# Acoustic_Cam.net
KiCad netlist of a schematic drawn in Altium Designer
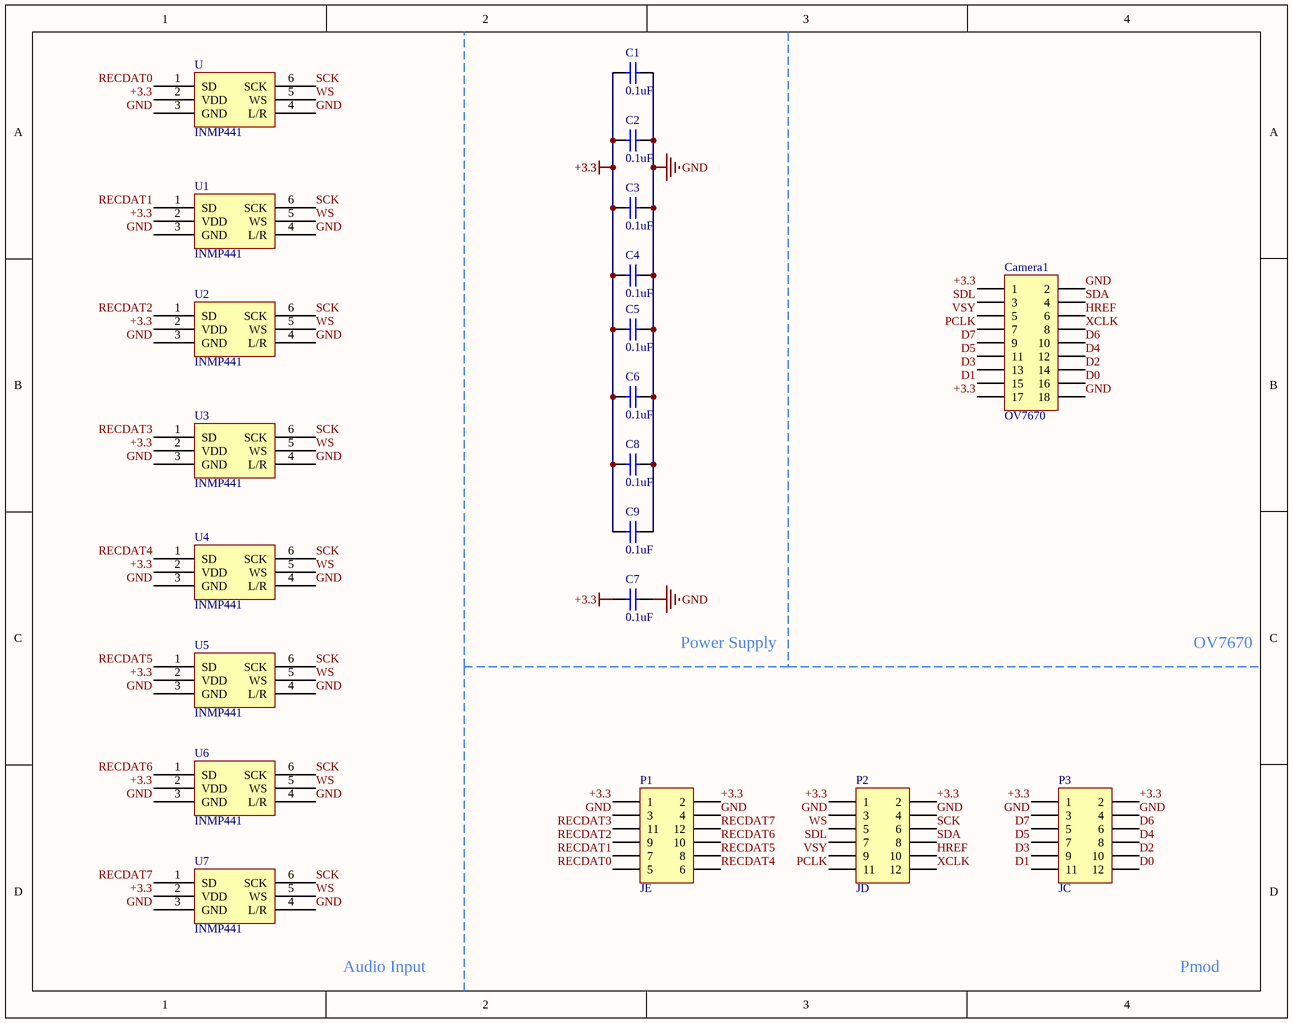
[diagram p0: Acoustic_Cam.SchDoc]

(export (version "E")
  (design (tool "Eeschema 10.0.6"))
  (components
    (comp (ref "C1")
      (value "0.1uF")
      (footprint "0603-1")
      (description "Capacitor")
      (fields (field (name "PUBLISHER") "Altium Limited"))
      (libsource (lib "Miscellaneous Devices") (part "Cap"))
    )
    (comp (ref "C2")
      (value "0.1uF")
      (footprint "0603-1")
      (description "Capacitor")
      (fields (field (name "PUBLISHER") "Altium Limited"))
      (libsource (lib "Miscellaneous Devices") (part "Cap"))
    )
    (comp (ref "C3")
      (value "0.1uF")
      (footprint "0603-1")
      (description "Capacitor")
      (fields (field (name "PUBLISHER") "Altium Limited"))
      (libsource (lib "Miscellaneous Devices") (part "Cap"))
    )
    (comp (ref "C4")
      (value "0.1uF")
      (footprint "0603-1")
      (description "Capacitor")
      (fields (field (name "PUBLISHER") "Altium Limited"))
      (libsource (lib "Miscellaneous Devices") (part "Cap"))
    )
    (comp (ref "C5")
      (value "0.1uF")
      (footprint "0603-1")
      (description "Capacitor")
      (fields (field (name "PUBLISHER") "Altium Limited"))
      (libsource (lib "Miscellaneous Devices") (part "Cap"))
    )
    (comp (ref "C6")
      (value "0.1uF")
      (footprint "0603-1")
      (description "Capacitor")
      (fields (field (name "PUBLISHER") "Altium Limited"))
      (libsource (lib "Miscellaneous Devices") (part "Cap"))
    )
    (comp (ref "C7")
      (value "0.1uF")
      (footprint "0603-1")
      (description "Capacitor")
      (fields (field (name "PUBLISHER") "Altium Limited"))
      (libsource (lib "Miscellaneous Devices") (part "Cap"))
    )
    (comp (ref "C8")
      (value "0.1uF")
      (footprint "0603-1")
      (description "Capacitor")
      (fields (field (name "PUBLISHER") "Altium Limited"))
      (libsource (lib "Miscellaneous Devices") (part "Cap"))
    )
    (comp (ref "C9")
      (value "0.1uF")
      (footprint "0603-1")
      (description "Capacitor")
      (fields (field (name "PUBLISHER") "Altium Limited"))
      (libsource (lib "Miscellaneous Devices") (part "Cap"))
    )
    (comp (ref "Camera1")
      (value "OV7670")
      (footprint "HDR2X9")
      (description "Header, 9-Pin, Dual row")
      (fields (field (name "PUBLISHER") "Altium Limited"))
      (libsource (lib "Miscellaneous Connectors") (part "Header 9X2"))
    )
    (comp (ref "P1")
      (value "JE")
      (footprint "HDR2X6")
      (description "Header, 6-Pin, Dual row")
      (fields (field (name "PUBLISHER") "Altium Limited"))
      (libsource (lib "") (part "Header 6X2_1"))
    )
    (comp (ref "P2")
      (value "JD")
      (footprint "HDR2X6")
      (description "Header, 6-Pin, Dual row")
      (fields (field (name "PUBLISHER") "Altium Limited"))
      (libsource (lib "Miscellaneous Connectors") (part "Header 6X2"))
    )
    (comp (ref "P3")
      (value "JC")
      (footprint "HDR2X6")
      (description "Header, 6-Pin, Dual row")
      (fields (field (name "PUBLISHER") "Altium Limited"))
      (libsource (lib "Miscellaneous Connectors") (part "Header 6X2"))
    )
    (comp (ref "U") (value "INMP441") (footprint "INMP441board") (libsource (lib "Schlib2") (part "INMP441")))
    (comp (ref "U1")
      (value "INMP441")
      (footprint "INMP441board")
      (libsource (lib "Schlib2") (part "INMP441"))
    )
    (comp (ref "U2")
      (value "INMP441")
      (footprint "INMP441board")
      (libsource (lib "Schlib2") (part "INMP441"))
    )
    (comp (ref "U3")
      (value "INMP441")
      (footprint "INMP441board")
      (libsource (lib "Schlib2") (part "INMP441"))
    )
    (comp (ref "U4")
      (value "INMP441")
      (footprint "INMP441board")
      (libsource (lib "Schlib2") (part "INMP441"))
    )
    (comp (ref "U5")
      (value "INMP441")
      (footprint "INMP441board")
      (libsource (lib "Schlib2") (part "INMP441"))
    )
    (comp (ref "U6")
      (value "INMP441")
      (footprint "INMP441board")
      (libsource (lib "Schlib2") (part "INMP441"))
    )
    (comp (ref "U7")
      (value "INMP441")
      (footprint "INMP441board")
      (libsource (lib "Schlib2") (part "INMP441"))
    )
  )
  (nets
    (net (code "1") (name "+3.3") (class "Default")
      (node (ref "C1") (pin "1") (pinfunction "1_1") (pintype "passive"))
      (node (ref "C2") (pin "1") (pinfunction "1_1") (pintype "passive"))
      (node (ref "C3") (pin "1") (pinfunction "1_1") (pintype "passive"))
      (node (ref "C4") (pin "1") (pinfunction "1_1") (pintype "passive"))
      (node (ref "C5") (pin "1") (pinfunction "1_1") (pintype "passive"))
      (node (ref "C6") (pin "1") (pinfunction "1_1") (pintype "passive"))
      (node (ref "C7") (pin "1") (pinfunction "1_1") (pintype "passive"))
      (node (ref "C8") (pin "1") (pinfunction "1_1") (pintype "passive"))
      (node (ref "C9") (pin "1") (pinfunction "1_1") (pintype "passive"))
      (node (ref "Camera1") (pin "1") (pinfunction "1_1") (pintype "passive"))
      (node (ref "Camera1") (pin "17") (pinfunction "17_17") (pintype "passive"))
      (node (ref "P1") (pin "1") (pinfunction "1_1") (pintype "passive"))
      (node (ref "P1") (pin "2") (pinfunction "2_2") (pintype "passive"))
      (node (ref "P2") (pin "1") (pinfunction "1_1") (pintype "passive"))
      (node (ref "P2") (pin "2") (pinfunction "2_2") (pintype "passive"))
      (node (ref "P3") (pin "1") (pinfunction "1_1") (pintype "passive"))
      (node (ref "P3") (pin "2") (pinfunction "2_2") (pintype "passive"))
      (node (ref "U") (pin "2") (pinfunction "VDD_2") (pintype "passive"))
      (node (ref "U1") (pin "2") (pinfunction "VDD_2") (pintype "passive"))
      (node (ref "U2") (pin "2") (pinfunction "VDD_2") (pintype "passive"))
      (node (ref "U3") (pin "2") (pinfunction "VDD_2") (pintype "passive"))
      (node (ref "U4") (pin "2") (pinfunction "VDD_2") (pintype "passive"))
      (node (ref "U5") (pin "2") (pinfunction "VDD_2") (pintype "passive"))
      (node (ref "U6") (pin "2") (pinfunction "VDD_2") (pintype "passive"))
      (node (ref "U7") (pin "2") (pinfunction "VDD_2") (pintype "passive"))
    )
    (net (code "2") (name "/D0") (class "Default")
      (node (ref "Camera1") (pin "16") (pinfunction "16_16") (pintype "passive"))
      (node (ref "P3") (pin "12") (pinfunction "12_12") (pintype "passive"))
    )
    (net (code "3") (name "/D1") (class "Default")
      (node (ref "Camera1") (pin "15") (pinfunction "15_15") (pintype "passive"))
      (node (ref "P3") (pin "11") (pinfunction "11_11") (pintype "passive"))
    )
    (net (code "4") (name "/D2") (class "Default")
      (node (ref "Camera1") (pin "14") (pinfunction "14_14") (pintype "passive"))
      (node (ref "P3") (pin "10") (pinfunction "10_10") (pintype "passive"))
    )
    (net (code "5") (name "/D3") (class "Default")
      (node (ref "Camera1") (pin "13") (pinfunction "13_13") (pintype "passive"))
      (node (ref "P3") (pin "9") (pinfunction "9_9") (pintype "passive"))
    )
    (net (code "6") (name "/D4") (class "Default")
      (node (ref "Camera1") (pin "12") (pinfunction "12_12") (pintype "passive"))
      (node (ref "P3") (pin "8") (pinfunction "8_8") (pintype "passive"))
    )
    (net (code "7") (name "/D5") (class "Default")
      (node (ref "Camera1") (pin "11") (pinfunction "11_11") (pintype "passive"))
      (node (ref "P3") (pin "7") (pinfunction "7_7") (pintype "passive"))
    )
    (net (code "8") (name "/D6") (class "Default")
      (node (ref "Camera1") (pin "10") (pinfunction "10_10") (pintype "passive"))
      (node (ref "P3") (pin "6") (pinfunction "6_6") (pintype "passive"))
    )
    (net (code "9") (name "/D7") (class "Default")
      (node (ref "Camera1") (pin "9") (pinfunction "9_9") (pintype "passive"))
      (node (ref "P3") (pin "5") (pinfunction "5_5") (pintype "passive"))
    )
    (net (code "10") (name "/HREF") (class "Default")
      (node (ref "Camera1") (pin "6") (pinfunction "6_6") (pintype "passive"))
      (node (ref "P2") (pin "10") (pinfunction "10_10") (pintype "passive"))
    )
    (net (code "11") (name "/PCLK") (class "Default")
      (node (ref "Camera1") (pin "7") (pinfunction "7_7") (pintype "passive"))
      (node (ref "P2") (pin "11") (pinfunction "11_11") (pintype "passive"))
    )
    (net (code "12") (name "/RECDAT0") (class "Default")
      (node (ref "P1") (pin "5") (pinfunction "5_5") (pintype "passive"))
      (node (ref "U") (pin "1") (pinfunction "SD_1") (pintype "passive"))
    )
    (net (code "13") (name "/RECDAT1") (class "Default")
      (node (ref "P1") (pin "7") (pinfunction "7_7") (pintype "passive"))
      (node (ref "U1") (pin "1") (pinfunction "SD_1") (pintype "passive"))
    )
    (net (code "14") (name "/RECDAT2") (class "Default")
      (node (ref "P1") (pin "9") (pinfunction "9_9") (pintype "passive"))
      (node (ref "U2") (pin "1") (pinfunction "SD_1") (pintype "passive"))
    )
    (net (code "15") (name "/RECDAT3") (class "Default")
      (node (ref "P1") (pin "11") (pinfunction "11_11") (pintype "passive"))
      (node (ref "U3") (pin "1") (pinfunction "SD_1") (pintype "passive"))
    )
    (net (code "16") (name "/RECDAT4") (class "Default")
      (node (ref "P1") (pin "6") (pinfunction "6_6") (pintype "passive"))
      (node (ref "U4") (pin "1") (pinfunction "SD_1") (pintype "passive"))
    )
    (net (code "17") (name "/RECDAT5") (class "Default")
      (node (ref "P1") (pin "8") (pinfunction "8_8") (pintype "passive"))
      (node (ref "U5") (pin "1") (pinfunction "SD_1") (pintype "passive"))
    )
    (net (code "18") (name "/RECDAT6") (class "Default")
      (node (ref "P1") (pin "10") (pinfunction "10_10") (pintype "passive"))
      (node (ref "U6") (pin "1") (pinfunction "SD_1") (pintype "passive"))
    )
    (net (code "19") (name "/RECDAT7") (class "Default")
      (node (ref "P1") (pin "12") (pinfunction "12_12") (pintype "passive"))
      (node (ref "U7") (pin "1") (pinfunction "SD_1") (pintype "passive"))
    )
    (net (code "20") (name "/SCK") (class "Default")
      (node (ref "P2") (pin "6") (pinfunction "6_6") (pintype "passive"))
      (node (ref "U") (pin "6") (pinfunction "SCK_6") (pintype "passive"))
      (node (ref "U1") (pin "6") (pinfunction "SCK_6") (pintype "passive"))
      (node (ref "U2") (pin "6") (pinfunction "SCK_6") (pintype "passive"))
      (node (ref "U3") (pin "6") (pinfunction "SCK_6") (pintype "passive"))
      (node (ref "U4") (pin "6") (pinfunction "SCK_6") (pintype "passive"))
      (node (ref "U5") (pin "6") (pinfunction "SCK_6") (pintype "passive"))
      (node (ref "U6") (pin "6") (pinfunction "SCK_6") (pintype "passive"))
      (node (ref "U7") (pin "6") (pinfunction "SCK_6") (pintype "passive"))
    )
    (net (code "21") (name "/SDA") (class "Default")
      (node (ref "Camera1") (pin "4") (pinfunction "4_4") (pintype "passive"))
      (node (ref "P2") (pin "8") (pinfunction "8_8") (pintype "passive"))
    )
    (net (code "22") (name "/SDL") (class "Default")
      (node (ref "Camera1") (pin "3") (pinfunction "3_3") (pintype "passive"))
      (node (ref "P2") (pin "7") (pinfunction "7_7") (pintype "passive"))
    )
    (net (code "23") (name "/VSY") (class "Default")
      (node (ref "Camera1") (pin "5") (pinfunction "5_5") (pintype "passive"))
      (node (ref "P2") (pin "9") (pinfunction "9_9") (pintype "passive"))
    )
    (net (code "24") (name "/WS") (class "Default")
      (node (ref "P2") (pin "5") (pinfunction "5_5") (pintype "passive"))
      (node (ref "U") (pin "5") (pinfunction "WS_5") (pintype "passive"))
      (node (ref "U1") (pin "5") (pinfunction "WS_5") (pintype "passive"))
      (node (ref "U2") (pin "5") (pinfunction "WS_5") (pintype "passive"))
      (node (ref "U3") (pin "5") (pinfunction "WS_5") (pintype "passive"))
      (node (ref "U4") (pin "5") (pinfunction "WS_5") (pintype "passive"))
      (node (ref "U5") (pin "5") (pinfunction "WS_5") (pintype "passive"))
      (node (ref "U6") (pin "5") (pinfunction "WS_5") (pintype "passive"))
      (node (ref "U7") (pin "5") (pinfunction "WS_5") (pintype "passive"))
    )
    (net (code "25") (name "/XCLK") (class "Default")
      (node (ref "Camera1") (pin "8") (pinfunction "8_8") (pintype "passive"))
      (node (ref "P2") (pin "12") (pinfunction "12_12") (pintype "passive"))
    )
    (net (code "26") (name "GND") (class "Default")
      (node (ref "C1") (pin "2") (pinfunction "2_2") (pintype "passive"))
      (node (ref "C2") (pin "2") (pinfunction "2_2") (pintype "passive"))
      (node (ref "C3") (pin "2") (pinfunction "2_2") (pintype "passive"))
      (node (ref "C4") (pin "2") (pinfunction "2_2") (pintype "passive"))
      (node (ref "C5") (pin "2") (pinfunction "2_2") (pintype "passive"))
      (node (ref "C6") (pin "2") (pinfunction "2_2") (pintype "passive"))
      (node (ref "C7") (pin "2") (pinfunction "2_2") (pintype "passive"))
      (node (ref "C8") (pin "2") (pinfunction "2_2") (pintype "passive"))
      (node (ref "C9") (pin "2") (pinfunction "2_2") (pintype "passive"))
      (node (ref "Camera1") (pin "18") (pinfunction "18_18") (pintype "passive"))
      (node (ref "Camera1") (pin "2") (pinfunction "2_2") (pintype "passive"))
      (node (ref "P1") (pin "3") (pinfunction "3_3") (pintype "passive"))
      (node (ref "P1") (pin "4") (pinfunction "4_4") (pintype "passive"))
      (node (ref "P2") (pin "3") (pinfunction "3_3") (pintype "passive"))
      (node (ref "P2") (pin "4") (pinfunction "4_4") (pintype "passive"))
      (node (ref "P3") (pin "3") (pinfunction "3_3") (pintype "passive"))
      (node (ref "P3") (pin "4") (pinfunction "4_4") (pintype "passive"))
      (node (ref "U") (pin "3") (pinfunction "GND_3") (pintype "passive"))
      (node (ref "U") (pin "4") (pinfunction "L/R_4") (pintype "passive"))
      (node (ref "U1") (pin "3") (pinfunction "GND_3") (pintype "passive"))
      (node (ref "U1") (pin "4") (pinfunction "L/R_4") (pintype "passive"))
      (node (ref "U2") (pin "3") (pinfunction "GND_3") (pintype "passive"))
      (node (ref "U2") (pin "4") (pinfunction "L/R_4") (pintype "passive"))
      (node (ref "U3") (pin "3") (pinfunction "GND_3") (pintype "passive"))
      (node (ref "U3") (pin "4") (pinfunction "L/R_4") (pintype "passive"))
      (node (ref "U4") (pin "3") (pinfunction "GND_3") (pintype "passive"))
      (node (ref "U4") (pin "4") (pinfunction "L/R_4") (pintype "passive"))
      (node (ref "U5") (pin "3") (pinfunction "GND_3") (pintype "passive"))
      (node (ref "U5") (pin "4") (pinfunction "L/R_4") (pintype "passive"))
      (node (ref "U6") (pin "3") (pinfunction "GND_3") (pintype "passive"))
      (node (ref "U6") (pin "4") (pinfunction "L/R_4") (pintype "passive"))
      (node (ref "U7") (pin "3") (pinfunction "GND_3") (pintype "passive"))
      (node (ref "U7") (pin "4") (pinfunction "L/R_4") (pintype "passive"))
    )
  )
)
